# nes2p.net
KiCad netlist of a schematic drawn in EAGLE
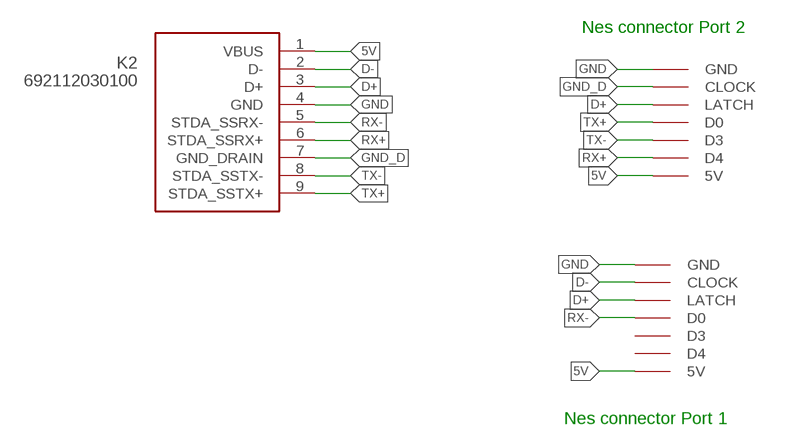
[diagram p0: schematic, sheet 1]

(export (version "E")
  (design (tool "Eeschema 10.0.6"))
  (components
    (comp (ref "K2")
      (value "692112030100")
      (footprint "eagle-import:692112030100")
      (libsource (lib "eagle-import") (part "692112030100"))
    )
    (comp (ref "U$1")
      (value "NESCONNNO_TABS")
      (footprint "eagle-import:NESCONN_NO_TABS")
      (libsource (lib "eagle-import") (part "NESCONNNO_TABS"))
    )
    (comp (ref "U$2")
      (value "NESCONNNO_TABS")
      (footprint "eagle-import:NESCONN_NO_TABS")
      (libsource (lib "eagle-import") (part "NESCONNNO_TABS"))
    )
  )
  (nets
    (net (code "1") (name "5V") (class "Default")
      (node (ref "K2") (pin "1") (pinfunction "VBUS_1") (pintype "bidirectional"))
      (node (ref "U$1") (pin "5V") (pinfunction "5V_5V") (pintype "power_in"))
      (node (ref "U$2") (pin "5V") (pinfunction "5V_5V") (pintype "power_in"))
    )
    (net (code "2") (name "D+") (class "Default")
      (node (ref "K2") (pin "3") (pinfunction "D+_3") (pintype "bidirectional"))
      (node (ref "U$1") (pin "LATCH") (pinfunction "LATCH_LATCH") (pintype "input"))
      (node (ref "U$2") (pin "LATCH") (pinfunction "LATCH_LATCH") (pintype "input"))
    )
    (net (code "3") (name "D-") (class "Default")
      (node (ref "K2") (pin "2") (pinfunction "D-_2") (pintype "bidirectional"))
      (node (ref "U$2") (pin "CLOCK") (pinfunction "CLOCK_CLOCK") (pintype "input"))
    )
    (net (code "4") (name "GND") (class "Default")
      (node (ref "K2") (pin "4") (pinfunction "GND_4") (pintype "bidirectional"))
      (node (ref "U$1") (pin "GND") (pinfunction "GND_GND") (pintype "input"))
      (node (ref "U$2") (pin "GND") (pinfunction "GND_GND") (pintype "input"))
    )
    (net (code "5") (name "GND_D") (class "Default")
      (node (ref "K2") (pin "7") (pinfunction "GND_DRAIN_7") (pintype "bidirectional"))
      (node (ref "U$1") (pin "CLOCK") (pinfunction "CLOCK_CLOCK") (pintype "input"))
    )
    (net (code "6") (name "RX+") (class "Default")
      (node (ref "K2") (pin "6") (pinfunction "STDA_SSRX+_6") (pintype "bidirectional"))
      (node (ref "U$1") (pin "D4") (pinfunction "D4_D4") (pintype "bidirectional"))
    )
    (net (code "7") (name "RX-") (class "Default")
      (node (ref "K2") (pin "5") (pinfunction "STDA_SSRX-_5") (pintype "bidirectional"))
      (node (ref "U$2") (pin "D0") (pinfunction "D0_D0") (pintype "bidirectional"))
    )
    (net (code "8") (name "TX+") (class "Default")
      (node (ref "K2") (pin "9") (pinfunction "STDA_SSTX+_9") (pintype "bidirectional"))
      (node (ref "U$1") (pin "D0") (pinfunction "D0_D0") (pintype "bidirectional"))
    )
    (net (code "9") (name "TX-") (class "Default")
      (node (ref "K2") (pin "8") (pinfunction "STDA_SSTX-_8") (pintype "bidirectional"))
      (node (ref "U$1") (pin "D3") (pinfunction "D3_D3") (pintype "bidirectional"))
    )
    (net (code "10") (name "unconnected-(U$2-PadD3)") (class "Default")
      (node (ref "U$2") (pin "D3") (pinfunction "D3_D3") (pintype "bidirectional"))
    )
    (net (code "11") (name "unconnected-(U$2-PadD4)") (class "Default")
      (node (ref "U$2") (pin "D4") (pinfunction "D4_D4") (pintype "bidirectional"))
    )
  )
)
